# Wheelspeed_rev11_v2.net
KiCad netlist of a schematic drawn in EAGLE
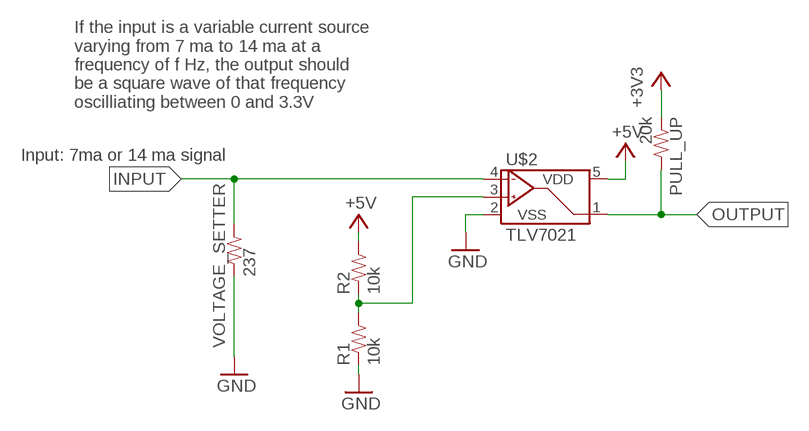
[diagram p0: schematic, sheet 1]

(export (version "E")
  (design (tool "Eeschema 10.0.6"))
  (components
    (comp (ref "PULL_UP")
      (value "20k")
      (footprint "eagle-import:0603-RES")
      (libsource (lib "eagle-import") (part "RESISTOR0603"))
    )
    (comp (ref "R1")
      (value "10k")
      (footprint "eagle-import:0603-RES")
      (libsource (lib "eagle-import") (part "RESISTOR0603"))
    )
    (comp (ref "R2")
      (value "10k")
      (footprint "eagle-import:0603-RES")
      (libsource (lib "eagle-import") (part "RESISTOR0603"))
    )
    (comp (ref "U$2")
      (value "TLV7021")
      (footprint "eagle-import:SOT-23-5")
      (libsource (lib "eagle-import") (part "OPA990IDBVR"))
    )
    (comp (ref "VOLTAGE_SETTER")
      (value "237")
      (footprint "eagle-import:0603-RES")
      (libsource (lib "eagle-import") (part "RESISTOR0603"))
    )
  )
  (nets
    (net (code "1") (name "+3V3") (class "Default")
      (node (ref "PULL_UP") (pin "1") (pinfunction "1_1") (pintype "passive"))
    )
    (net (code "2") (name "+5V") (class "Default")
      (node (ref "R2") (pin "2") (pinfunction "2_2") (pintype "passive"))
      (node (ref "U$2") (pin "5") (pinfunction "VDD_5") (pintype "passive"))
    )
    (net (code "3") (name "GND") (class "Default")
      (node (ref "R1") (pin "1") (pinfunction "1_1") (pintype "passive"))
      (node (ref "U$2") (pin "2") (pinfunction "VSS_2") (pintype "passive"))
      (node (ref "VOLTAGE_SETTER") (pin "1") (pinfunction "1_1") (pintype "passive"))
    )
    (net (code "4") (name "INPUT") (class "Default")
      (node (ref "U$2") (pin "4") (pinfunction "VIN-_4") (pintype "passive"))
      (node (ref "VOLTAGE_SETTER") (pin "2") (pinfunction "2_2") (pintype "passive"))
    )
    (net (code "5") (name "Net-(U$2-VIN+)") (class "Default")
      (node (ref "R1") (pin "2") (pinfunction "2_2") (pintype "passive"))
      (node (ref "R2") (pin "1") (pinfunction "1_1") (pintype "passive"))
      (node (ref "U$2") (pin "3") (pinfunction "VIN+_3") (pintype "passive"))
    )
    (net (code "6") (name "OUTPUT") (class "Default")
      (node (ref "PULL_UP") (pin "2") (pinfunction "2_2") (pintype "passive"))
      (node (ref "U$2") (pin "1") (pinfunction "VOUT_1") (pintype "passive"))
    )
  )
)
